# Super-Regenerative-FM_old.net
KiCad netlist of a schematic drawn in EAGLE
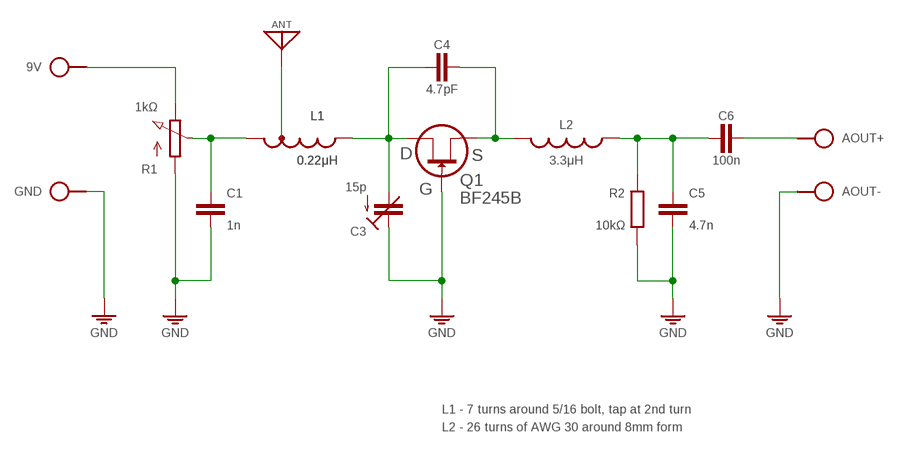
[diagram p0: schematic, sheet 1]

(export (version "E")
  (design (tool "Eeschema 10.0.6"))
  (components
    (comp (ref "9V")
      (value "SPAD")
      (footprint "eagle-import:SPAD")
      (libsource (lib "eagle-import") (part "SPAD"))
    )
    (comp (ref "ANT")
      (value "ANT")
      (footprint "eagle-import:SPAD")
      (libsource (lib "eagle-import") (part "ANT"))
    )
    (comp (ref "AOUT+")
      (value "SPAD")
      (footprint "eagle-import:SPAD")
      (libsource (lib "eagle-import") (part "SPAD"))
    )
    (comp (ref "AOUT-")
      (value "SPAD")
      (footprint "eagle-import:SPAD")
      (libsource (lib "eagle-import") (part "SPAD"))
    )
    (comp (ref "C1")
      (value "1n")
      (footprint "eagle-import:C050-020X036_V")
      (libsource (lib "eagle-import") (part "C050-020X036/V"))
    )
    (comp (ref "C3")
      (value "15p")
      (footprint "eagle-import:TRIM-2222-808")
      (libsource (lib "eagle-import") (part "C-TR-PH201272222-808-2PIN"))
    )
    (comp (ref "C4")
      (value "4.7pF")
      (footprint "eagle-import:C050-020X036")
      (libsource (lib "eagle-import") (part "C050-020X036"))
    )
    (comp (ref "C5")
      (value "4.7n")
      (footprint "eagle-import:C050-020X044")
      (libsource (lib "eagle-import") (part "C050-020X044"))
    )
    (comp (ref "C6")
      (value "100n")
      (footprint "eagle-import:C050-020X044")
      (libsource (lib "eagle-import") (part "C050-020X044"))
    )
    (comp (ref "GND")
      (value "SPAD")
      (footprint "eagle-import:SPAD")
      (libsource (lib "eagle-import") (part "SPAD"))
    )
    (comp (ref "L1")
      (value "0.22μH")
      (footprint "eagle-import:L-08_12-X-TAP1")
      (libsource (lib "eagle-import") (part "L-TAP1L-08/12-X-TAP1"))
    )
    (comp (ref "L2")
      (value "3.3μH")
      (footprint "eagle-import:L-BODY")
      (libsource (lib "eagle-import") (part "L-BODY"))
    )
    (comp (ref "Q1")
      (value "BF245B")
      (footprint "eagle-import:TO92")
      (libsource (lib "eagle-import") (part "BF245B"))
    )
    (comp (ref "R1")
      (value "1kΩ")
      (footprint "eagle-import:POT-V")
      (libsource (lib "eagle-import") (part "POT-V"))
    )
    (comp (ref "R2")
      (value "10kΩ")
      (footprint "eagle-import:0204_10")
      (libsource (lib "eagle-import") (part "R0204/10"))
    )
  )
  (nets
    (net (code "1") (name "GND") (class "Default")
      (node (ref "AOUT-") (pin "1") (pinfunction "P$1_1") (pintype "bidirectional"))
      (node (ref "C1") (pin "2") (pinfunction "2_2") (pintype "passive"))
      (node (ref "C3") (pin "1") (pinfunction "E_1") (pintype "passive"))
      (node (ref "C5") (pin "2") (pinfunction "2_2") (pintype "passive"))
      (node (ref "GND") (pin "1") (pinfunction "P$1_1") (pintype "bidirectional"))
      (node (ref "Q1") (pin "1") (pinfunction "G_1") (pintype "passive"))
      (node (ref "R1") (pin "A") (pinfunction "A_A") (pintype "passive"))
      (node (ref "R2") (pin "1") (pinfunction "1_1") (pintype "passive"))
    )
    (net (code "2") (name "Net-(9V-P$1)") (class "Default")
      (node (ref "9V") (pin "1") (pinfunction "P$1_1") (pintype "bidirectional"))
      (node (ref "R1") (pin "E") (pinfunction "E_E") (pintype "passive"))
    )
    (net (code "3") (name "Net-(AOUT+-P$1)") (class "Default")
      (node (ref "AOUT+") (pin "1") (pinfunction "P$1_1") (pintype "bidirectional"))
      (node (ref "C6") (pin "2") (pinfunction "2_2") (pintype "passive"))
    )
    (net (code "4") (name "Net-(C1-Pad1)") (class "Default")
      (node (ref "C1") (pin "1") (pinfunction "1_1") (pintype "passive"))
      (node (ref "L1") (pin "1") (pinfunction "1_1") (pintype "passive"))
      (node (ref "R1") (pin "S") (pinfunction "S_S") (pintype "passive"))
    )
    (net (code "5") (name "Net-(C3-A)") (class "Default")
      (node (ref "C3") (pin "2") (pinfunction "A_2") (pintype "passive"))
      (node (ref "C4") (pin "1") (pinfunction "1_1") (pintype "passive"))
      (node (ref "L1") (pin "2") (pinfunction "2_2") (pintype "passive"))
      (node (ref "Q1") (pin "3") (pinfunction "D_3") (pintype "passive"))
    )
    (net (code "6") (name "Net-(L1-T)") (class "Default")
      (node (ref "ANT") (pin "1") (pinfunction "1_1") (pintype "output"))
      (node (ref "L1") (pin "3") (pinfunction "T_3") (pintype "passive"))
    )
    (net (code "7") (name "Net-(L2-1)") (class "Default")
      (node (ref "C5") (pin "1") (pinfunction "1_1") (pintype "passive"))
      (node (ref "C6") (pin "1") (pinfunction "1_1") (pintype "passive"))
      (node (ref "L2") (pin "2") (pinfunction "1_2") (pintype "passive"))
      (node (ref "R2") (pin "2") (pinfunction "2_2") (pintype "passive"))
    )
    (net (code "8") (name "Net-(L2-2)") (class "Default")
      (node (ref "C4") (pin "2") (pinfunction "2_2") (pintype "passive"))
      (node (ref "L2") (pin "3") (pinfunction "2_3") (pintype "passive"))
      (node (ref "Q1") (pin "2") (pinfunction "S_2") (pintype "passive"))
    )
  )
)
